# Photocoupler12Vinput.net
KiCad netlist of a schematic drawn in Altium Designer
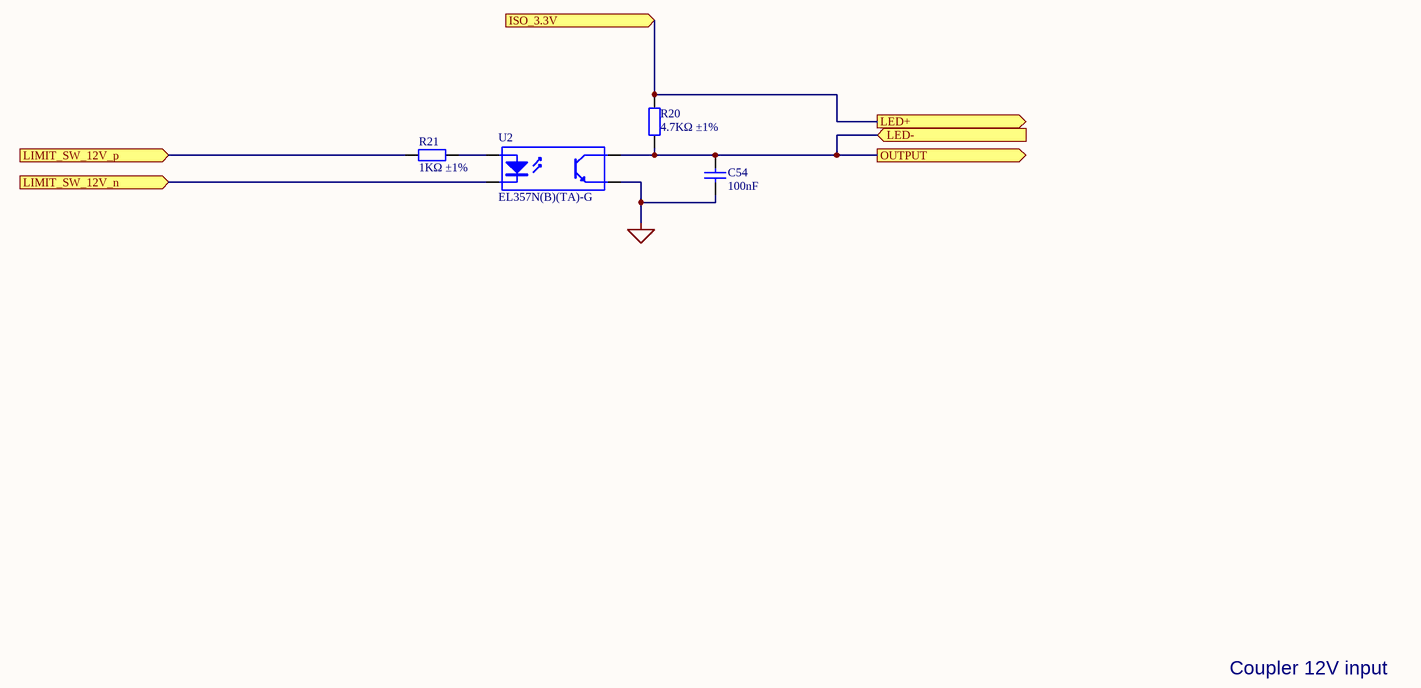
[diagram p0: Photocoupler12Vinput.SchDoc]

(export (version "E")
  (design (tool "Eeschema 10.0.6"))
  (components
    (comp (ref "C54")
      (value "100nF")
      (footprint "0603_C")
      (description "Chip capacitors")
      (fields (field (name "MANUFACTURER") "YAGEO") (field (name "PARTNUMBER") "CC0603KRX7R9BB104"))
      (libsource (lib "Cap") (part "0603 100nF (104) 10% 50V"))
    )
    (comp (ref "R20")
      (value "4.7KΩ ±1%")
      (footprint "0603_R")
      (description "Chip resistor")
      (fields (field (name "MANUFACTURER") "Uniroyal Elec") (field (name "PARTNUMBER") "0603WAF4701T5E"))
      (libsource (lib "RES") (part "0603 4.7K (4701) 1%"))
    )
    (comp (ref "R21")
      (value "1KΩ ±1%")
      (footprint "0603_R")
      (description "Chip resistor")
      (fields (field (name "MANUFACTURER") "Uniroyal Elec") (field (name "PARTNUMBER") "0603WAF1001T5E"))
      (libsource (lib "RES") (part "0603 1K (1001) 1%"))
    )
    (comp (ref "U2")
      (value "EL357N(B)(TA)-G")
      (footprint "Miscellaneous Devices LC:SOP-4_P2.54")
      (description "OPTOISOLATOR 3.75KV TRANS 4-SOP")
      (libsource (lib "IC") (part "EL357N(B)(TA)-G_[C6649]"))
    )
  )
  (nets
    (net (code "1") (name "/ISO_3.3V") (class "Default")
      (node (ref "R20") (pin "2") (pinfunction "2_2") (pintype "passive"))
    )
    (net (code "2") (name "/LED-") (class "Default")
      (node (ref "C54") (pin "2") (pinfunction "2_2") (pintype "passive"))
      (node (ref "R20") (pin "1") (pinfunction "1_1") (pintype "passive"))
      (node (ref "U2") (pin "4") (pinfunction "C_4") (pintype "passive"))
    )
    (net (code "3") (name "/LIMIT_SW_12V_n") (class "Default")
      (node (ref "U2") (pin "2") (pinfunction "K_2") (pintype "passive"))
    )
    (net (code "4") (name "/LIMIT_SW_12V_p") (class "Default")
      (node (ref "R21") (pin "1") (pinfunction "1_1") (pintype "passive"))
    )
    (net (code "5") (name "MCU_GND") (class "Default")
      (node (ref "C54") (pin "1") (pinfunction "1_1") (pintype "passive"))
      (node (ref "U2") (pin "3") (pinfunction "E_3") (pintype "passive"))
    )
    (net (code "6") (name "Net-(U2-A)") (class "Default")
      (node (ref "R21") (pin "2") (pinfunction "2_2") (pintype "passive"))
      (node (ref "U2") (pin "1") (pinfunction "A_1") (pintype "passive"))
    )
  )
)
